# main.net
KiCad netlist of a schematic drawn in EAGLE
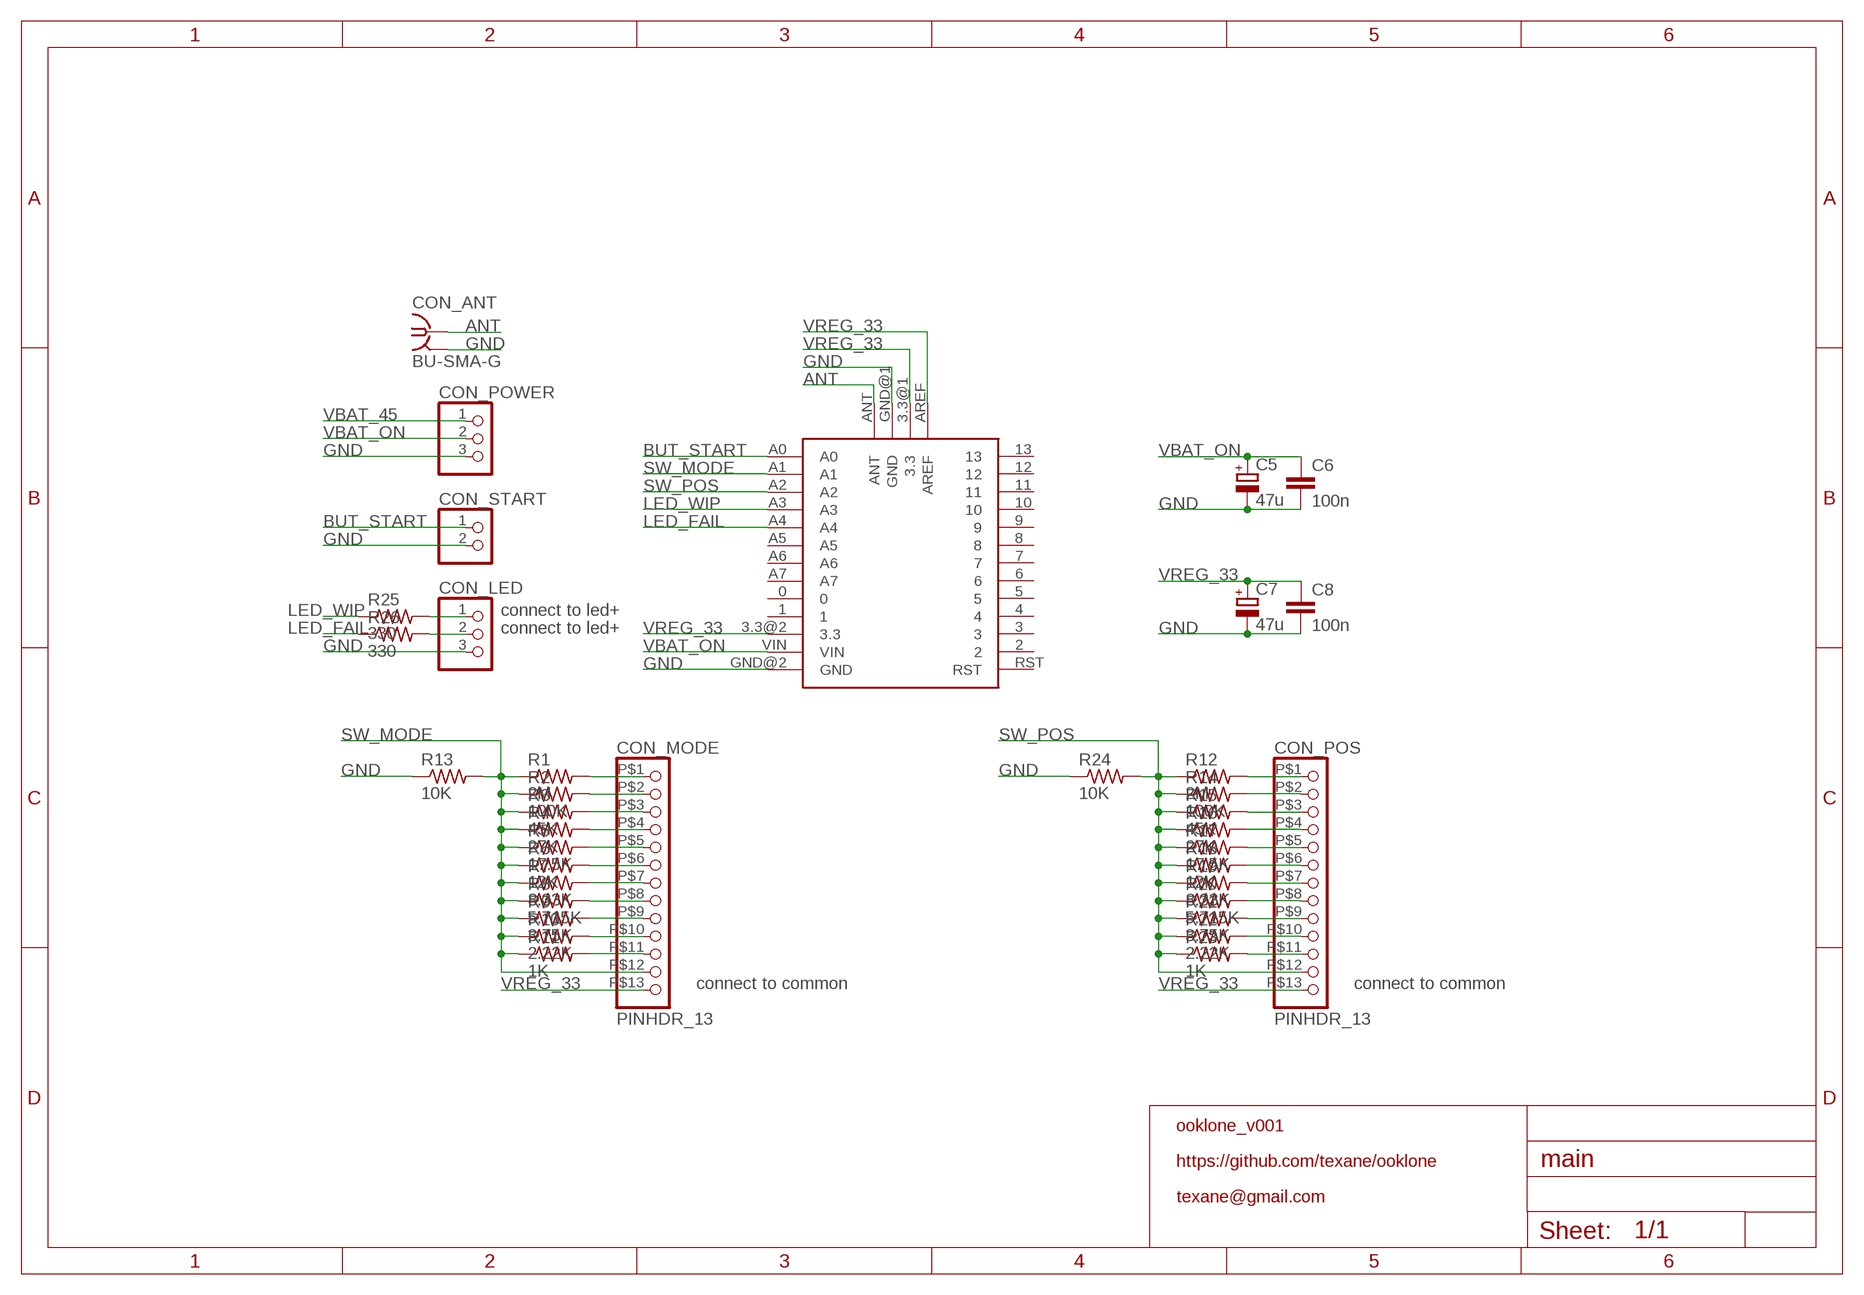
[diagram p0: schematic, sheet 1]

(export (version "E")
  (design (tool "Eeschema 10.0.6"))
  (components
    (comp (ref "C5")
      (value "47u")
      (footprint "eagle-import:PANASONIC_D")
      (libsource (lib "eagle-import") (part "CPOL-EUD"))
    )
    (comp (ref "C6")
      (value "100n")
      (footprint "eagle-import:C1206K")
      (libsource (lib "eagle-import") (part "C-EUC1206K"))
    )
    (comp (ref "C7")
      (value "47u")
      (footprint "eagle-import:PANASONIC_D")
      (libsource (lib "eagle-import") (part "CPOL-EUD"))
    )
    (comp (ref "C8")
      (value "100n")
      (footprint "eagle-import:C1206K")
      (libsource (lib "eagle-import") (part "C-EUC1206K"))
    )
    (comp (ref "CON_ANT")
      (value "BU-SMA-G")
      (footprint "eagle-import:BU-SMA-G")
      (libsource (lib "eagle-import") (part "BU-SMA-G"))
    )
    (comp (ref "CON_LED")
      (value "PINHD-1X3")
      (footprint "eagle-import:1X03")
      (libsource (lib "eagle-import") (part "PINHD-1X3"))
    )
    (comp (ref "CON_MODE")
      (value "PINHDR_13")
      (footprint "eagle-import:PINHDR_13")
      (libsource (lib "eagle-import") (part "PINHDR_13"))
    )
    (comp (ref "CON_POS")
      (value "PINHDR_13")
      (footprint "eagle-import:PINHDR_13")
      (libsource (lib "eagle-import") (part "PINHDR_13"))
    )
    (comp (ref "CON_POWER")
      (value "PINHD-1X3")
      (footprint "eagle-import:1X03")
      (libsource (lib "eagle-import") (part "PINHD-1X3"))
    )
    (comp (ref "CON_START")
      (value "PINHD-1X2")
      (footprint "eagle-import:1X02")
      (libsource (lib "eagle-import") (part "PINHD-1X2"))
    )
    (comp (ref "R1")
      (value "2M")
      (footprint "eagle-import:R1206")
      (libsource (lib "eagle-import") (part "R-US_R1206"))
    )
    (comp (ref "R2")
      (value "100K")
      (footprint "eagle-import:R1206")
      (libsource (lib "eagle-import") (part "R-US_R1206"))
    )
    (comp (ref "R3")
      (value "45K")
      (footprint "eagle-import:R1206")
      (libsource (lib "eagle-import") (part "R-US_R1206"))
    )
    (comp (ref "R4")
      (value "27K")
      (footprint "eagle-import:R1206")
      (libsource (lib "eagle-import") (part "R-US_R1206"))
    )
    (comp (ref "R5")
      (value "17.5K")
      (footprint "eagle-import:R1206")
      (libsource (lib "eagle-import") (part "R-US_R1206"))
    )
    (comp (ref "R6")
      (value "12K")
      (footprint "eagle-import:R1206")
      (libsource (lib "eagle-import") (part "R-US_R1206"))
    )
    (comp (ref "R7")
      (value "8.33K")
      (footprint "eagle-import:R1206")
      (libsource (lib "eagle-import") (part "R-US_R1206"))
    )
    (comp (ref "R8")
      (value "5.715K")
      (footprint "eagle-import:R1206")
      (libsource (lib "eagle-import") (part "R-US_R1206"))
    )
    (comp (ref "R9")
      (value "3.75K")
      (footprint "eagle-import:R1206")
      (libsource (lib "eagle-import") (part "R-US_R1206"))
    )
    (comp (ref "R10")
      (value "2.22K")
      (footprint "eagle-import:R1206")
      (libsource (lib "eagle-import") (part "R-US_R1206"))
    )
    (comp (ref "R11")
      (value "1K")
      (footprint "eagle-import:R1206")
      (libsource (lib "eagle-import") (part "R-US_R1206"))
    )
    (comp (ref "R12")
      (value "2M")
      (footprint "eagle-import:R1206")
      (libsource (lib "eagle-import") (part "R-US_R1206"))
    )
    (comp (ref "R13")
      (value "10K")
      (footprint "eagle-import:R1206")
      (libsource (lib "eagle-import") (part "R-US_R1206"))
    )
    (comp (ref "R14")
      (value "100K")
      (footprint "eagle-import:R1206")
      (libsource (lib "eagle-import") (part "R-US_R1206"))
    )
    (comp (ref "R15")
      (value "45K")
      (footprint "eagle-import:R1206")
      (libsource (lib "eagle-import") (part "R-US_R1206"))
    )
    (comp (ref "R16")
      (value "27K")
      (footprint "eagle-import:R1206")
      (libsource (lib "eagle-import") (part "R-US_R1206"))
    )
    (comp (ref "R17")
      (value "17.5K")
      (footprint "eagle-import:R1206")
      (libsource (lib "eagle-import") (part "R-US_R1206"))
    )
    (comp (ref "R18")
      (value "12K")
      (footprint "eagle-import:R1206")
      (libsource (lib "eagle-import") (part "R-US_R1206"))
    )
    (comp (ref "R19")
      (value "8.33K")
      (footprint "eagle-import:R1206")
      (libsource (lib "eagle-import") (part "R-US_R1206"))
    )
    (comp (ref "R20")
      (value "5.715K")
      (footprint "eagle-import:R1206")
      (libsource (lib "eagle-import") (part "R-US_R1206"))
    )
    (comp (ref "R21")
      (value "3.75K")
      (footprint "eagle-import:R1206")
      (libsource (lib "eagle-import") (part "R-US_R1206"))
    )
    (comp (ref "R22")
      (value "2.22K")
      (footprint "eagle-import:R1206")
      (libsource (lib "eagle-import") (part "R-US_R1206"))
    )
    (comp (ref "R23")
      (value "1K")
      (footprint "eagle-import:R1206")
      (libsource (lib "eagle-import") (part "R-US_R1206"))
    )
    (comp (ref "R24")
      (value "10K")
      (footprint "eagle-import:R1206")
      (libsource (lib "eagle-import") (part "R-US_R1206"))
    )
    (comp (ref "R25")
      (value "330")
      (footprint "eagle-import:R1206")
      (libsource (lib "eagle-import") (part "R-US_R1206"))
    )
    (comp (ref "R26")
      (value "330")
      (footprint "eagle-import:R1206")
      (libsource (lib "eagle-import") (part "R-US_R1206"))
    )
    (comp (ref "U$1")
      (value "MOTEINO_USB_R4")
      (footprint "eagle-import:MOTEINO_USB_R4")
      (libsource (lib "eagle-import") (part "MOTEINO_USB_R4"))
    )
  )
  (nets
    (net (code "1") (name "/ANT") (class "Default")
      (node (ref "CON_ANT") (pin "1") (pinfunction "1_1") (pintype "passive"))
      (node (ref "U$1") (pin "ANT") (pinfunction "ANT_ANT") (pintype "bidirectional"))
    )
    (net (code "2") (name "/BUT_START") (class "Default")
      (node (ref "CON_START") (pin "1") (pinfunction "1_1") (pintype "passive"))
      (node (ref "U$1") (pin "A0") (pinfunction "A0_A0") (pintype "bidirectional"))
    )
    (net (code "3") (name "/GND") (class "Default")
      (node (ref "C5") (pin "-") (pinfunction "-_-") (pintype "passive"))
      (node (ref "C6") (pin "2") (pinfunction "2_2") (pintype "passive"))
      (node (ref "C7") (pin "-") (pinfunction "-_-") (pintype "passive"))
      (node (ref "C8") (pin "2") (pinfunction "2_2") (pintype "passive"))
      (node (ref "CON_ANT") (pin "2") (pinfunction "2_2") (pintype "passive"))
      (node (ref "CON_ANT") (pin "3") (pinfunction "2_3") (pintype "passive"))
      (node (ref "CON_ANT") (pin "4") (pinfunction "2_4") (pintype "passive"))
      (node (ref "CON_ANT") (pin "5") (pinfunction "2_5") (pintype "passive"))
      (node (ref "CON_LED") (pin "3") (pinfunction "3_3") (pintype "passive"))
      (node (ref "CON_POWER") (pin "3") (pinfunction "3_3") (pintype "passive"))
      (node (ref "CON_START") (pin "2") (pinfunction "2_2") (pintype "passive"))
      (node (ref "R13") (pin "1") (pinfunction "1_1") (pintype "passive"))
      (node (ref "R24") (pin "1") (pinfunction "1_1") (pintype "passive"))
      (node (ref "U$1") (pin "GND@1") (pinfunction "GND_GND@1") (pintype "bidirectional"))
      (node (ref "U$1") (pin "GND@2") (pinfunction "GND_GND@2") (pintype "bidirectional"))
    )
    (net (code "4") (name "/LED_FAIL") (class "Default")
      (node (ref "R26") (pin "1") (pinfunction "1_1") (pintype "passive"))
      (node (ref "U$1") (pin "A4") (pinfunction "A4_A4") (pintype "bidirectional"))
    )
    (net (code "5") (name "/LED_WIP") (class "Default")
      (node (ref "R25") (pin "1") (pinfunction "1_1") (pintype "passive"))
      (node (ref "U$1") (pin "A3") (pinfunction "A3_A3") (pintype "bidirectional"))
    )
    (net (code "6") (name "/SW_MODE") (class "Default")
      (node (ref "CON_MODE") (pin "P$12") (pinfunction "12_P$12") (pintype "passive"))
      (node (ref "R1") (pin "1") (pinfunction "1_1") (pintype "passive"))
      (node (ref "R10") (pin "1") (pinfunction "1_1") (pintype "passive"))
      (node (ref "R11") (pin "1") (pinfunction "1_1") (pintype "passive"))
      (node (ref "R13") (pin "2") (pinfunction "2_2") (pintype "passive"))
      (node (ref "R2") (pin "1") (pinfunction "1_1") (pintype "passive"))
      (node (ref "R3") (pin "1") (pinfunction "1_1") (pintype "passive"))
      (node (ref "R4") (pin "1") (pinfunction "1_1") (pintype "passive"))
      (node (ref "R5") (pin "1") (pinfunction "1_1") (pintype "passive"))
      (node (ref "R6") (pin "1") (pinfunction "1_1") (pintype "passive"))
      (node (ref "R7") (pin "1") (pinfunction "1_1") (pintype "passive"))
      (node (ref "R8") (pin "1") (pinfunction "1_1") (pintype "passive"))
      (node (ref "R9") (pin "1") (pinfunction "1_1") (pintype "passive"))
      (node (ref "U$1") (pin "A1") (pinfunction "A1_A1") (pintype "bidirectional"))
    )
    (net (code "7") (name "/SW_POS") (class "Default")
      (node (ref "CON_POS") (pin "P$12") (pinfunction "12_P$12") (pintype "passive"))
      (node (ref "R12") (pin "1") (pinfunction "1_1") (pintype "passive"))
      (node (ref "R14") (pin "1") (pinfunction "1_1") (pintype "passive"))
      (node (ref "R15") (pin "1") (pinfunction "1_1") (pintype "passive"))
      (node (ref "R16") (pin "1") (pinfunction "1_1") (pintype "passive"))
      (node (ref "R17") (pin "1") (pinfunction "1_1") (pintype "passive"))
      (node (ref "R18") (pin "1") (pinfunction "1_1") (pintype "passive"))
      (node (ref "R19") (pin "1") (pinfunction "1_1") (pintype "passive"))
      (node (ref "R20") (pin "1") (pinfunction "1_1") (pintype "passive"))
      (node (ref "R21") (pin "1") (pinfunction "1_1") (pintype "passive"))
      (node (ref "R22") (pin "1") (pinfunction "1_1") (pintype "passive"))
      (node (ref "R23") (pin "1") (pinfunction "1_1") (pintype "passive"))
      (node (ref "R24") (pin "2") (pinfunction "2_2") (pintype "passive"))
      (node (ref "U$1") (pin "A2") (pinfunction "A2_A2") (pintype "bidirectional"))
    )
    (net (code "8") (name "/VBAT_45") (class "Default")
      (node (ref "CON_POWER") (pin "1") (pinfunction "1_1") (pintype "passive"))
    )
    (net (code "9") (name "/VBAT_ON") (class "Default")
      (node (ref "C5") (pin "+") (pinfunction "+_+") (pintype "passive"))
      (node (ref "C6") (pin "1") (pinfunction "1_1") (pintype "passive"))
      (node (ref "CON_POWER") (pin "2") (pinfunction "2_2") (pintype "passive"))
      (node (ref "U$1") (pin "VIN") (pinfunction "VIN_VIN") (pintype "bidirectional"))
    )
    (net (code "10") (name "/VREG_33") (class "Default")
      (node (ref "C7") (pin "+") (pinfunction "+_+") (pintype "passive"))
      (node (ref "C8") (pin "1") (pinfunction "1_1") (pintype "passive"))
      (node (ref "CON_MODE") (pin "P$13") (pinfunction "13_P$13") (pintype "passive"))
      (node (ref "CON_POS") (pin "P$13") (pinfunction "13_P$13") (pintype "passive"))
      (node (ref "U$1") (pin "3.3@1") (pinfunction "3.3_3.3@1") (pintype "bidirectional"))
      (node (ref "U$1") (pin "3.3@2") (pinfunction "3.3_3.3@2") (pintype "bidirectional"))
      (node (ref "U$1") (pin "AREF") (pinfunction "AREF_AREF") (pintype "bidirectional"))
    )
    (net (code "11") (name "Net-(CON_LED-Pad1)") (class "Default")
      (node (ref "CON_LED") (pin "1") (pinfunction "1_1") (pintype "passive"))
      (node (ref "R25") (pin "2") (pinfunction "2_2") (pintype "passive"))
    )
    (net (code "12") (name "Net-(CON_LED-Pad2)") (class "Default")
      (node (ref "CON_LED") (pin "2") (pinfunction "2_2") (pintype "passive"))
      (node (ref "R26") (pin "2") (pinfunction "2_2") (pintype "passive"))
    )
    (net (code "13") (name "Net-(CON_MODE-1)") (class "Default")
      (node (ref "CON_MODE") (pin "P$1") (pinfunction "1_P$1") (pintype "passive"))
      (node (ref "R1") (pin "2") (pinfunction "2_2") (pintype "passive"))
    )
    (net (code "14") (name "Net-(CON_MODE-2)") (class "Default")
      (node (ref "CON_MODE") (pin "P$2") (pinfunction "2_P$2") (pintype "passive"))
      (node (ref "R2") (pin "2") (pinfunction "2_2") (pintype "passive"))
    )
    (net (code "15") (name "Net-(CON_MODE-3)") (class "Default")
      (node (ref "CON_MODE") (pin "P$3") (pinfunction "3_P$3") (pintype "passive"))
      (node (ref "R3") (pin "2") (pinfunction "2_2") (pintype "passive"))
    )
    (net (code "16") (name "Net-(CON_MODE-4)") (class "Default")
      (node (ref "CON_MODE") (pin "P$4") (pinfunction "4_P$4") (pintype "passive"))
      (node (ref "R4") (pin "2") (pinfunction "2_2") (pintype "passive"))
    )
    (net (code "17") (name "Net-(CON_MODE-5)") (class "Default")
      (node (ref "CON_MODE") (pin "P$5") (pinfunction "5_P$5") (pintype "passive"))
      (node (ref "R5") (pin "2") (pinfunction "2_2") (pintype "passive"))
    )
    (net (code "18") (name "Net-(CON_MODE-6)") (class "Default")
      (node (ref "CON_MODE") (pin "P$6") (pinfunction "6_P$6") (pintype "passive"))
      (node (ref "R6") (pin "2") (pinfunction "2_2") (pintype "passive"))
    )
    (net (code "19") (name "Net-(CON_MODE-7)") (class "Default")
      (node (ref "CON_MODE") (pin "P$7") (pinfunction "7_P$7") (pintype "passive"))
      (node (ref "R7") (pin "2") (pinfunction "2_2") (pintype "passive"))
    )
    (net (code "20") (name "Net-(CON_MODE-8)") (class "Default")
      (node (ref "CON_MODE") (pin "P$8") (pinfunction "8_P$8") (pintype "passive"))
      (node (ref "R8") (pin "2") (pinfunction "2_2") (pintype "passive"))
    )
    (net (code "21") (name "Net-(CON_MODE-9)") (class "Default")
      (node (ref "CON_MODE") (pin "P$9") (pinfunction "9_P$9") (pintype "passive"))
      (node (ref "R9") (pin "2") (pinfunction "2_2") (pintype "passive"))
    )
    (net (code "22") (name "Net-(CON_MODE-10)") (class "Default")
      (node (ref "CON_MODE") (pin "P$10") (pinfunction "10_P$10") (pintype "passive"))
      (node (ref "R10") (pin "2") (pinfunction "2_2") (pintype "passive"))
    )
    (net (code "23") (name "Net-(CON_MODE-11)") (class "Default")
      (node (ref "CON_MODE") (pin "P$11") (pinfunction "11_P$11") (pintype "passive"))
      (node (ref "R11") (pin "2") (pinfunction "2_2") (pintype "passive"))
    )
    (net (code "24") (name "Net-(CON_POS-1)") (class "Default")
      (node (ref "CON_POS") (pin "P$1") (pinfunction "1_P$1") (pintype "passive"))
      (node (ref "R12") (pin "2") (pinfunction "2_2") (pintype "passive"))
    )
    (net (code "25") (name "Net-(CON_POS-2)") (class "Default")
      (node (ref "CON_POS") (pin "P$2") (pinfunction "2_P$2") (pintype "passive"))
      (node (ref "R14") (pin "2") (pinfunction "2_2") (pintype "passive"))
    )
    (net (code "26") (name "Net-(CON_POS-3)") (class "Default")
      (node (ref "CON_POS") (pin "P$3") (pinfunction "3_P$3") (pintype "passive"))
      (node (ref "R15") (pin "2") (pinfunction "2_2") (pintype "passive"))
    )
    (net (code "27") (name "Net-(CON_POS-4)") (class "Default")
      (node (ref "CON_POS") (pin "P$4") (pinfunction "4_P$4") (pintype "passive"))
      (node (ref "R16") (pin "2") (pinfunction "2_2") (pintype "passive"))
    )
    (net (code "28") (name "Net-(CON_POS-5)") (class "Default")
      (node (ref "CON_POS") (pin "P$5") (pinfunction "5_P$5") (pintype "passive"))
      (node (ref "R17") (pin "2") (pinfunction "2_2") (pintype "passive"))
    )
    (net (code "29") (name "Net-(CON_POS-6)") (class "Default")
      (node (ref "CON_POS") (pin "P$6") (pinfunction "6_P$6") (pintype "passive"))
      (node (ref "R18") (pin "2") (pinfunction "2_2") (pintype "passive"))
    )
    (net (code "30") (name "Net-(CON_POS-7)") (class "Default")
      (node (ref "CON_POS") (pin "P$7") (pinfunction "7_P$7") (pintype "passive"))
      (node (ref "R19") (pin "2") (pinfunction "2_2") (pintype "passive"))
    )
    (net (code "31") (name "Net-(CON_POS-8)") (class "Default")
      (node (ref "CON_POS") (pin "P$8") (pinfunction "8_P$8") (pintype "passive"))
      (node (ref "R20") (pin "2") (pinfunction "2_2") (pintype "passive"))
    )
    (net (code "32") (name "Net-(CON_POS-9)") (class "Default")
      (node (ref "CON_POS") (pin "P$9") (pinfunction "9_P$9") (pintype "passive"))
      (node (ref "R21") (pin "2") (pinfunction "2_2") (pintype "passive"))
    )
    (net (code "33") (name "Net-(CON_POS-10)") (class "Default")
      (node (ref "CON_POS") (pin "P$10") (pinfunction "10_P$10") (pintype "passive"))
      (node (ref "R22") (pin "2") (pinfunction "2_2") (pintype "passive"))
    )
    (net (code "34") (name "Net-(CON_POS-11)") (class "Default")
      (node (ref "CON_POS") (pin "P$11") (pinfunction "11_P$11") (pintype "passive"))
      (node (ref "R23") (pin "2") (pinfunction "2_2") (pintype "passive"))
    )
    (net (code "35") (name "unconnected-(U$1-Pad0)") (class "Default")
      (node (ref "U$1") (pin "0") (pinfunction "0_0") (pintype "bidirectional"))
    )
    (net (code "36") (name "unconnected-(U$1-Pad1)") (class "Default")
      (node (ref "U$1") (pin "1") (pinfunction "1_1") (pintype "bidirectional"))
    )
    (net (code "37") (name "unconnected-(U$1-Pad2)") (class "Default")
      (node (ref "U$1") (pin "2") (pinfunction "2_2") (pintype "bidirectional"))
    )
    (net (code "38") (name "unconnected-(U$1-Pad3)") (class "Default")
      (node (ref "U$1") (pin "3") (pinfunction "3_3") (pintype "bidirectional"))
    )
    (net (code "39") (name "unconnected-(U$1-Pad4)") (class "Default")
      (node (ref "U$1") (pin "4") (pinfunction "4_4") (pintype "bidirectional"))
    )
    (net (code "40") (name "unconnected-(U$1-Pad5)") (class "Default")
      (node (ref "U$1") (pin "5") (pinfunction "5_5") (pintype "bidirectional"))
    )
    (net (code "41") (name "unconnected-(U$1-Pad6)") (class "Default")
      (node (ref "U$1") (pin "6") (pinfunction "6_6") (pintype "bidirectional"))
    )
    (net (code "42") (name "unconnected-(U$1-Pad7)") (class "Default")
      (node (ref "U$1") (pin "7") (pinfunction "7_7") (pintype "bidirectional"))
    )
    (net (code "43") (name "unconnected-(U$1-Pad8)") (class "Default")
      (node (ref "U$1") (pin "8") (pinfunction "8_8") (pintype "bidirectional"))
    )
    (net (code "44") (name "unconnected-(U$1-Pad9)") (class "Default")
      (node (ref "U$1") (pin "9") (pinfunction "9_9") (pintype "bidirectional"))
    )
    (net (code "45") (name "unconnected-(U$1-Pad10)") (class "Default")
      (node (ref "U$1") (pin "10") (pinfunction "10_10") (pintype "bidirectional"))
    )
    (net (code "46") (name "unconnected-(U$1-Pad11)") (class "Default")
      (node (ref "U$1") (pin "11") (pinfunction "11_11") (pintype "bidirectional"))
    )
    (net (code "47") (name "unconnected-(U$1-Pad12)") (class "Default")
      (node (ref "U$1") (pin "12") (pinfunction "12_12") (pintype "bidirectional"))
    )
    (net (code "48") (name "unconnected-(U$1-Pad13)") (class "Default")
      (node (ref "U$1") (pin "13") (pinfunction "13_13") (pintype "bidirectional"))
    )
    (net (code "49") (name "unconnected-(U$1-PadA5)") (class "Default")
      (node (ref "U$1") (pin "A5") (pinfunction "A5_A5") (pintype "bidirectional"))
    )
    (net (code "50") (name "unconnected-(U$1-PadA6)") (class "Default")
      (node (ref "U$1") (pin "A6") (pinfunction "A6_A6") (pintype "bidirectional"))
    )
    (net (code "51") (name "unconnected-(U$1-PadA7)") (class "Default")
      (node (ref "U$1") (pin "A7") (pinfunction "A7_A7") (pintype "bidirectional"))
    )
    (net (code "52") (name "unconnected-(U$1-PadRST)") (class "Default")
      (node (ref "U$1") (pin "RST") (pinfunction "RST_RST") (pintype "bidirectional"))
    )
  )
)
